# Air_Quality.net
KiCad netlist of a schematic drawn in EAGLE
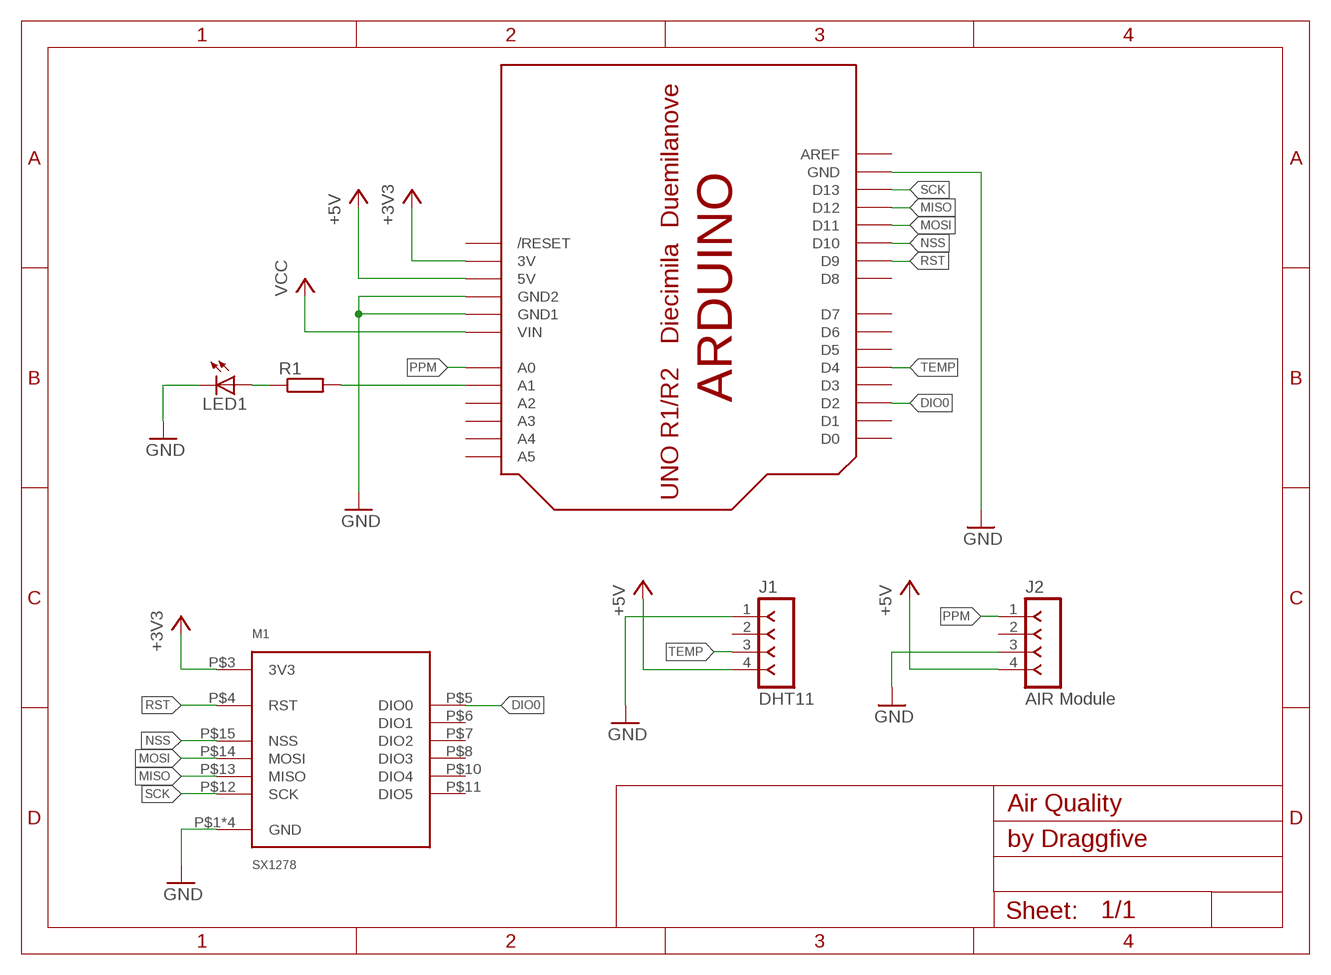
[diagram p0: schematic, sheet 1]

(export (version "E")
  (design (tool "Eeschema 10.0.6"))
  (components
    (comp (ref "J1")
      (value "DHT11")
      (footprint "eagle-import:SIP-100-04-32Y")
      (libsource (lib "eagle-import") (part "F-1X04-SIP-100-32Y"))
    )
    (comp (ref "J2")
      (value "AIR Module")
      (footprint "eagle-import:SIP-100-04-40Y")
      (libsource (lib "eagle-import") (part "F-1X04-SIP-100-40Y"))
    )
    (comp (ref "LED1")
      (value "LED5MM")
      (footprint "eagle-import:LED5MM")
      (libsource (lib "eagle-import") (part "LED5MM"))
    )
    (comp (ref "M1")
      (value "SX1278")
      (footprint "eagle-import:SX1278")
      (libsource (lib "eagle-import") (part "SX1278"))
    )
    (comp (ref "R1")
      (value "R-EU_0207/10")
      (footprint "eagle-import:0207_10")
      (libsource (lib "eagle-import") (part "R-EU_0207/10"))
    )
    (comp (ref "U$1")
      (value "ARDUINOUNO")
      (footprint "eagle-import:ARDUINO")
      (libsource (lib "eagle-import") (part "ARDUINOUNO"))
    )
  )
  (nets
    (net (code "1") (name "+3V3") (class "Default")
      (node (ref "M1") (pin "P$3") (pinfunction "3V3_P$3") (pintype "bidirectional"))
      (node (ref "U$1") (pin "3V") (pinfunction "3V_3V") (pintype "power_in"))
    )
    (net (code "2") (name "+5V") (class "Default")
      (node (ref "J1") (pin "4") (pinfunction "4_4") (pintype "passive"))
      (node (ref "J2") (pin "4") (pinfunction "4_4") (pintype "passive"))
      (node (ref "U$1") (pin "5V") (pinfunction "5V_5V") (pintype "power_in"))
    )
    (net (code "3") (name "DIO0") (class "Default")
      (node (ref "M1") (pin "P$5") (pinfunction "DIO0_P$5") (pintype "bidirectional"))
      (node (ref "U$1") (pin "D2") (pinfunction "D2_D2") (pintype "bidirectional"))
    )
    (net (code "4") (name "GND") (class "Default")
      (node (ref "J1") (pin "1") (pinfunction "1_1") (pintype "passive"))
      (node (ref "J2") (pin "3") (pinfunction "3_3") (pintype "passive"))
      (node (ref "LED1") (pin "K") (pinfunction "C_K") (pintype "passive"))
      (node (ref "M1") (pin "P$1") (pinfunction "GND_P$1") (pintype "bidirectional"))
      (node (ref "M1") (pin "P$16") (pinfunction "GND_P$16") (pintype "bidirectional"))
      (node (ref "M1") (pin "P$2") (pinfunction "GND_P$2") (pintype "bidirectional"))
      (node (ref "M1") (pin "P$9") (pinfunction "GND_P$9") (pintype "bidirectional"))
      (node (ref "U$1") (pin "GND") (pinfunction "GND_GND") (pintype "power_in"))
      (node (ref "U$1") (pin "GND1") (pinfunction "GND1_GND1") (pintype "power_in"))
      (node (ref "U$1") (pin "GND2") (pinfunction "GND2_GND2") (pintype "power_in"))
    )
    (net (code "5") (name "MISO") (class "Default")
      (node (ref "M1") (pin "P$13") (pinfunction "MISO_P$13") (pintype "bidirectional"))
      (node (ref "U$1") (pin "D12") (pinfunction "D12_D12") (pintype "bidirectional"))
    )
    (net (code "6") (name "MOSI") (class "Default")
      (node (ref "M1") (pin "P$14") (pinfunction "MOSI_P$14") (pintype "bidirectional"))
      (node (ref "U$1") (pin "D11") (pinfunction "D11_D11") (pintype "bidirectional"))
    )
    (net (code "7") (name "NSS") (class "Default")
      (node (ref "M1") (pin "P$15") (pinfunction "NSS_P$15") (pintype "bidirectional"))
      (node (ref "U$1") (pin "D10") (pinfunction "D10_D10") (pintype "bidirectional"))
    )
    (net (code "8") (name "Net-(LED1-PadA)") (class "Default")
      (node (ref "LED1") (pin "A") (pinfunction "A_A") (pintype "passive"))
      (node (ref "R1") (pin "1") (pinfunction "1_1") (pintype "passive"))
    )
    (net (code "9") (name "Net-(R1-Pad2)") (class "Default")
      (node (ref "R1") (pin "2") (pinfunction "2_2") (pintype "passive"))
      (node (ref "U$1") (pin "A1") (pinfunction "A1_A1") (pintype "bidirectional"))
    )
    (net (code "10") (name "PPM") (class "Default")
      (node (ref "J2") (pin "1") (pinfunction "1_1") (pintype "passive"))
      (node (ref "U$1") (pin "A0") (pinfunction "A0_A0") (pintype "bidirectional"))
    )
    (net (code "11") (name "RST") (class "Default")
      (node (ref "M1") (pin "P$4") (pinfunction "RST_P$4") (pintype "bidirectional"))
      (node (ref "U$1") (pin "D9") (pinfunction "D9_D9") (pintype "bidirectional"))
    )
    (net (code "12") (name "SCK") (class "Default")
      (node (ref "M1") (pin "P$12") (pinfunction "SCK_P$12") (pintype "bidirectional"))
      (node (ref "U$1") (pin "D13") (pinfunction "D13_D13") (pintype "bidirectional"))
    )
    (net (code "13") (name "TEMP") (class "Default")
      (node (ref "J1") (pin "3") (pinfunction "3_3") (pintype "passive"))
      (node (ref "U$1") (pin "D4") (pinfunction "D4_D4") (pintype "bidirectional"))
    )
    (net (code "14") (name "VCC") (class "Default")
      (node (ref "U$1") (pin "VIN") (pinfunction "VIN_VIN") (pintype "power_in"))
    )
    (net (code "15") (name "unconnected-(J1-Pad2)") (class "Default")
      (node (ref "J1") (pin "2") (pinfunction "2_2") (pintype "passive"))
    )
    (net (code "16") (name "unconnected-(J2-Pad2)") (class "Default")
      (node (ref "J2") (pin "2") (pinfunction "2_2") (pintype "passive"))
    )
    (net (code "17") (name "unconnected-(M1-DIO1-PadP$6)") (class "Default")
      (node (ref "M1") (pin "P$6") (pinfunction "DIO1_P$6") (pintype "bidirectional"))
    )
    (net (code "18") (name "unconnected-(M1-DIO2-PadP$7)") (class "Default")
      (node (ref "M1") (pin "P$7") (pinfunction "DIO2_P$7") (pintype "bidirectional"))
    )
    (net (code "19") (name "unconnected-(M1-DIO3-PadP$8)") (class "Default")
      (node (ref "M1") (pin "P$8") (pinfunction "DIO3_P$8") (pintype "bidirectional"))
    )
    (net (code "20") (name "unconnected-(M1-DIO4-PadP$10)") (class "Default")
      (node (ref "M1") (pin "P$10") (pinfunction "DIO4_P$10") (pintype "bidirectional"))
    )
    (net (code "21") (name "unconnected-(M1-DIO5-PadP$11)") (class "Default")
      (node (ref "M1") (pin "P$11") (pinfunction "DIO5_P$11") (pintype "bidirectional"))
    )
    (net (code "22") (name "unconnected-(U$1-PadA2)") (class "Default")
      (node (ref "U$1") (pin "A2") (pinfunction "A2_A2") (pintype "bidirectional"))
    )
    (net (code "23") (name "unconnected-(U$1-PadA3)") (class "Default")
      (node (ref "U$1") (pin "A3") (pinfunction "A3_A3") (pintype "bidirectional"))
    )
    (net (code "24") (name "unconnected-(U$1-PadA4)") (class "Default")
      (node (ref "U$1") (pin "A4") (pinfunction "A4_A4") (pintype "bidirectional"))
    )
    (net (code "25") (name "unconnected-(U$1-PadA5)") (class "Default")
      (node (ref "U$1") (pin "A5") (pinfunction "A5_A5") (pintype "bidirectional"))
    )
    (net (code "26") (name "unconnected-(U$1-PadAREF)") (class "Default")
      (node (ref "U$1") (pin "AREF") (pinfunction "AREF_AREF") (pintype "bidirectional"))
    )
    (net (code "27") (name "unconnected-(U$1-PadD0)") (class "Default")
      (node (ref "U$1") (pin "D0") (pinfunction "D0_D0") (pintype "bidirectional"))
    )
    (net (code "28") (name "unconnected-(U$1-PadD1)") (class "Default")
      (node (ref "U$1") (pin "D1") (pinfunction "D1_D1") (pintype "bidirectional"))
    )
    (net (code "29") (name "unconnected-(U$1-PadD3)") (class "Default")
      (node (ref "U$1") (pin "D3") (pinfunction "D3_D3") (pintype "bidirectional"))
    )
    (net (code "30") (name "unconnected-(U$1-PadD5)") (class "Default")
      (node (ref "U$1") (pin "D5") (pinfunction "D5_D5") (pintype "bidirectional"))
    )
    (net (code "31") (name "unconnected-(U$1-PadD6)") (class "Default")
      (node (ref "U$1") (pin "D6") (pinfunction "D6_D6") (pintype "bidirectional"))
    )
    (net (code "32") (name "unconnected-(U$1-PadD7)") (class "Default")
      (node (ref "U$1") (pin "D7") (pinfunction "D7_D7") (pintype "bidirectional"))
    )
    (net (code "33") (name "unconnected-(U$1-PadD8)") (class "Default")
      (node (ref "U$1") (pin "D8") (pinfunction "D8_D8") (pintype "bidirectional"))
    )
    (net (code "34") (name "unconnected-(U$1-{slash}RESET-PadRESET)") (class "Default")
      (node (ref "U$1") (pin "RESET") (pinfunction "/RESET_RESET") (pintype "bidirectional"))
    )
  )
)
